# Power.net
KiCad netlist of a schematic drawn in Altium Designer
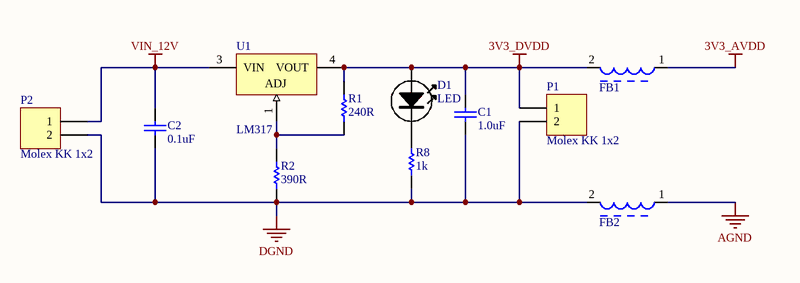
[diagram p0: Power.SchDoc]

(export (version "E")
  (design (tool "Eeschema 10.0.6"))
  (components
    (comp (ref "C1")
      (value "1.0uF")
      (footprint "C0805")
      (description "0805 Capacitor")
      (libsource (lib "PARSEC") (part "C0805"))
    )
    (comp (ref "C2")
      (value "0.1uF")
      (footprint "C0805")
      (description "0805 Capacitor")
      (libsource (lib "PARSEC") (part "C0805"))
    )
    (comp (ref "D1")
      (value "LED")
      (footprint "0805LED")
      (fields
        (field (name "MANUFACTURER") "OSRAM Opto Semiconductors Inc")
        (field (name "MANUFACTURER PART NUMBER") "LS T676-Q1R2-1-Z")
      )
      (libsource (lib "PARSEC") (part "LED"))
    )
    (comp (ref "FB1")
      (value "FERRITE")
      (footprint "R0805")
      (description "FERRITE BEAD 0805")
      (libsource (lib "PARSEC") (part "FERRITE"))
    )
    (comp (ref "FB2")
      (value "FERRITE")
      (footprint "R0805")
      (description "FERRITE BEAD 0805")
      (libsource (lib "PARSEC") (part "FERRITE"))
    )
    (comp (ref "P1")
      (value "Molex KK 1x2")
      (footprint "Molex KK 2x1")
      (description "1x2 Molex KK Connector")
      (libsource (lib "PARSEC") (part "Molex KK 1x2"))
    )
    (comp (ref "P2")
      (value "Molex KK 1x2")
      (footprint "Molex KK 2x1")
      (description "1x2 Molex KK Connector")
      (libsource (lib "") (part "Molex KK 1x2_1"))
    )
    (comp (ref "R1")
      (value "240R")
      (footprint "R0805")
      (description "RESISTOR 0805")
      (libsource (lib "PARSEC") (part "R0805"))
    )
    (comp (ref "R2")
      (value "390R")
      (footprint "R0805")
      (description "RESISTOR 0805")
      (libsource (lib "PARSEC") (part "R0805"))
    )
    (comp (ref "R8")
      (value "1k")
      (footprint "R0805")
      (description "RESISTOR 0805")
      (libsource (lib "PARSEC") (part "R0805"))
    )
    (comp (ref "U1")
      (value "LM317")
      (footprint "D-PAK")
      (description "Linear Voltage Regulator")
      (libsource (lib "PARSEC") (part "LM317"))
    )
  )
  (nets
    (net (code "1") (name "3V3_AVDD") (class "Default")
      (node (ref "FB1") (pin "1") (pinfunction "1_1") (pintype "passive"))
    )
    (net (code "2") (name "3V3_DVDD") (class "Default")
      (node (ref "C1") (pin "1") (pinfunction "1_1") (pintype "passive"))
      (node (ref "D1") (pin "A") (pintype "passive"))
      (node (ref "FB1") (pin "2") (pinfunction "2_2") (pintype "passive"))
      (node (ref "P1") (pin "1") (pinfunction "1_1") (pintype "passive"))
      (node (ref "R1") (pin "2") (pinfunction "2_2") (pintype "passive"))
      (node (ref "U1") (pin "4") (pinfunction "VOUT_4") (pintype "power_in"))
    )
    (net (code "3") (name "AGND") (class "Default")
      (node (ref "FB2") (pin "1") (pinfunction "1_1") (pintype "passive"))
    )
    (net (code "4") (name "DGND") (class "Default")
      (node (ref "C1") (pin "2") (pinfunction "2_2") (pintype "passive"))
      (node (ref "C2") (pin "2") (pinfunction "2_2") (pintype "passive"))
      (node (ref "FB2") (pin "2") (pinfunction "2_2") (pintype "passive"))
      (node (ref "P1") (pin "2") (pinfunction "2_2") (pintype "passive"))
      (node (ref "P2") (pin "2") (pinfunction "2_2") (pintype "passive"))
      (node (ref "R2") (pin "1") (pinfunction "1_1") (pintype "passive"))
      (node (ref "R8") (pin "1") (pinfunction "1_1") (pintype "passive"))
    )
    (net (code "5") (name "Net-(D1-PadK)") (class "Default")
      (node (ref "D1") (pin "K") (pintype "passive"))
      (node (ref "R8") (pin "2") (pinfunction "2_2") (pintype "passive"))
    )
    (net (code "6") (name "Net-(U1-ADJ)") (class "Default")
      (node (ref "R1") (pin "1") (pinfunction "1_1") (pintype "passive"))
      (node (ref "R2") (pin "2") (pinfunction "2_2") (pintype "passive"))
      (node (ref "U1") (pin "1") (pinfunction "ADJ_1") (pintype "input"))
    )
    (net (code "7") (name "VIN_12V") (class "Default")
      (node (ref "C2") (pin "1") (pinfunction "1_1") (pintype "passive"))
      (node (ref "P2") (pin "1") (pinfunction "1_1") (pintype "passive"))
      (node (ref "U1") (pin "3") (pinfunction "VIN_3") (pintype "power_in"))
    )
  )
)
